# 05-MODEM.net
KiCad netlist of a schematic drawn in Altium Designer
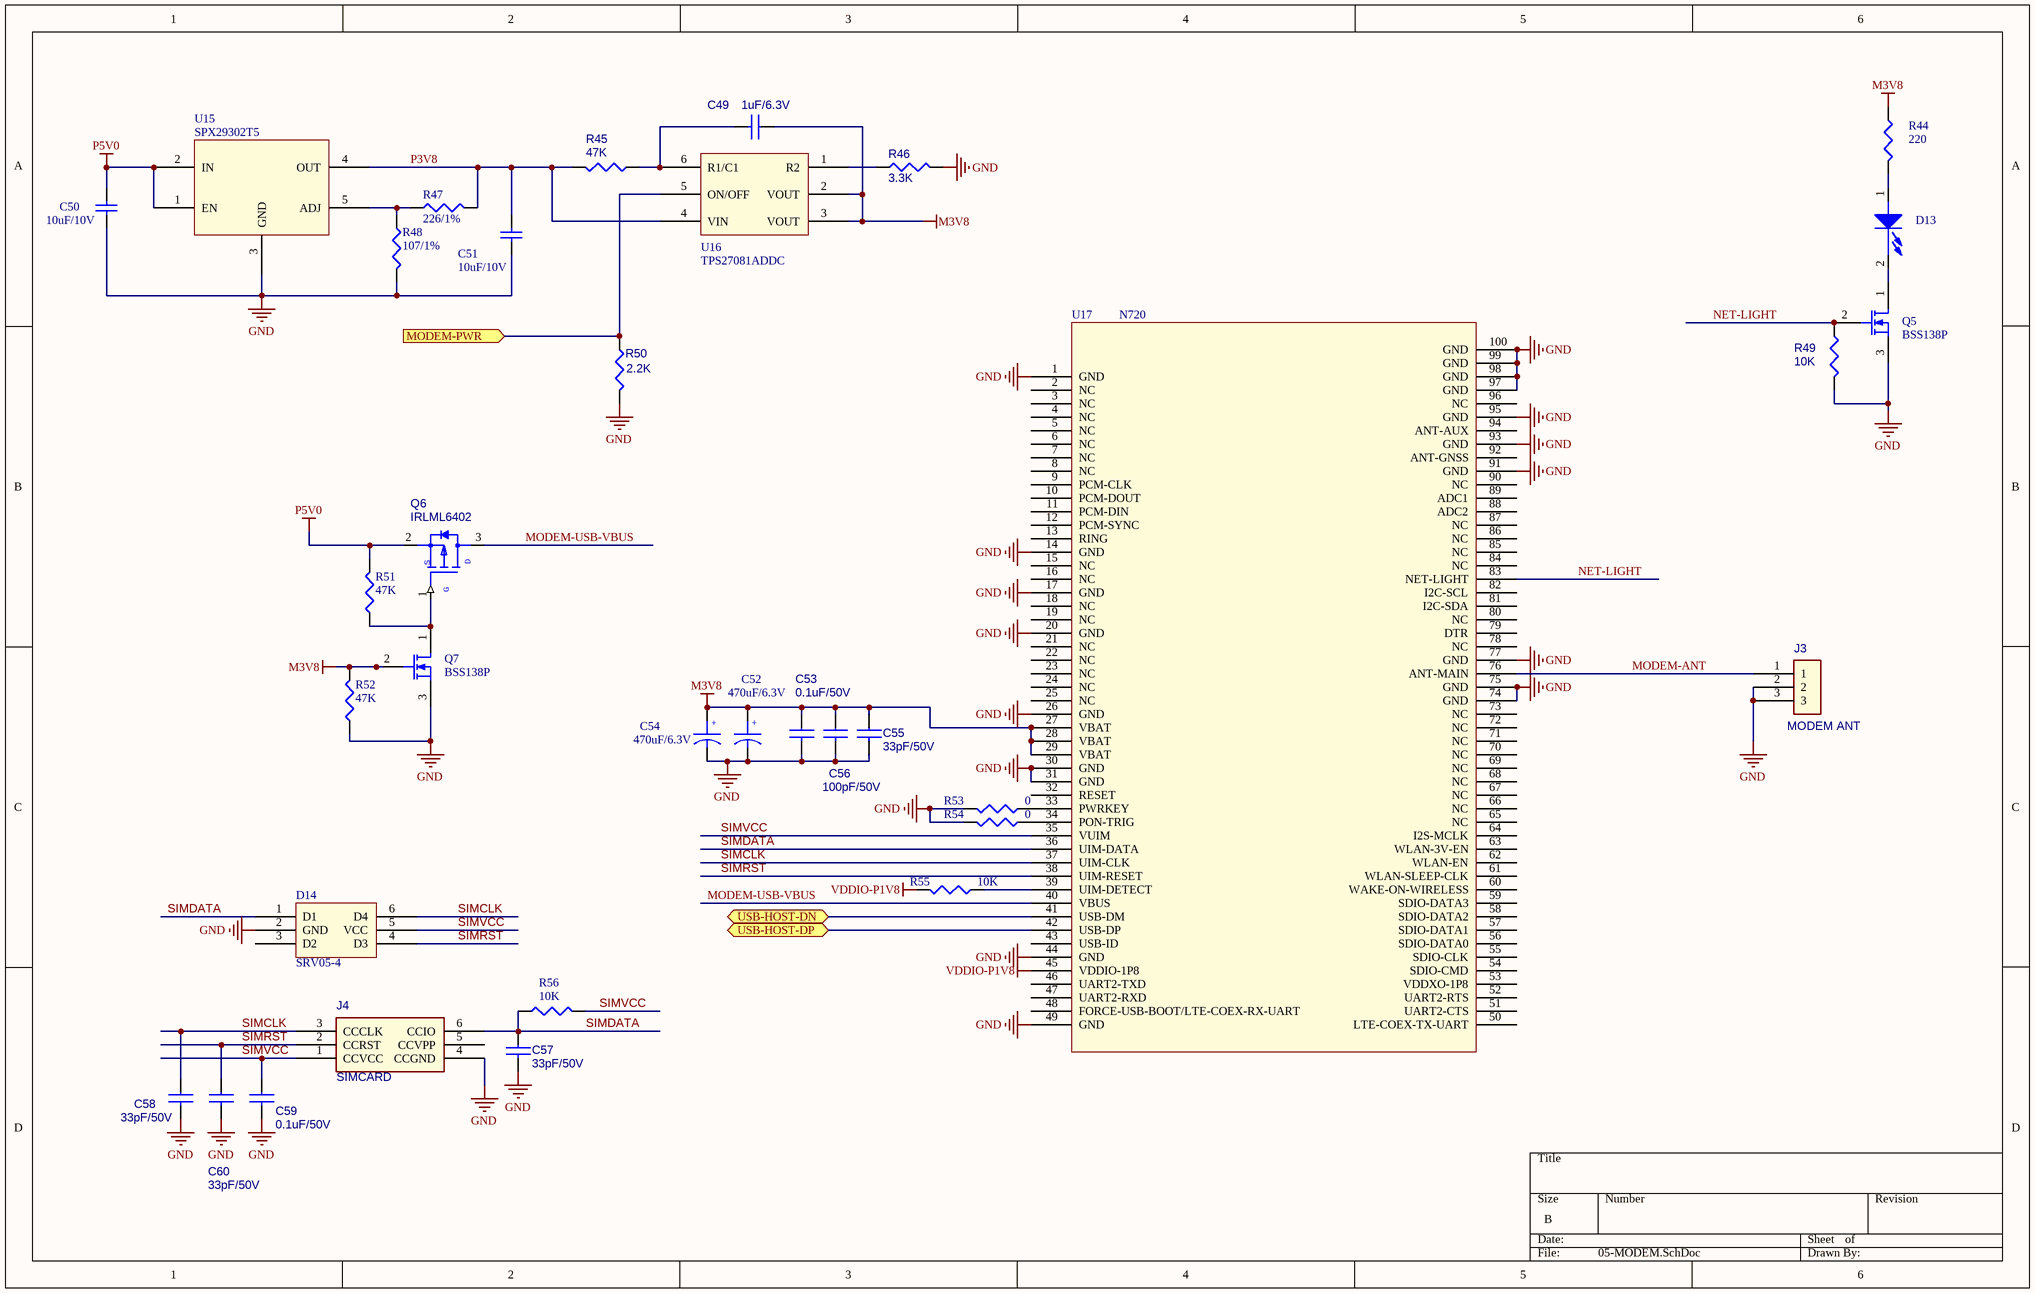
[diagram p0: 05-MODEM.SchDoc]

(export (version "E")
  (design (tool "Eeschema 10.0.6"))
  (components
    (comp (ref "C49") (value "1uF/6.3V") (footprint "0402") (libsource (lib "*") (part "P_CAP NP")))
    (comp (ref "C50")
      (value "10uF/10V")
      (footprint "0805")
      (description "Capacitor")
      (fields (field (name "PUBLISHER") "Altium Limited"))
      (libsource (lib "Miscellaneous Devices") (part "Cap"))
    )
    (comp (ref "C51")
      (value "10uF/10V")
      (footprint "0805")
      (description "Capacitor")
      (fields (field (name "PUBLISHER") "Altium Limited"))
      (libsource (lib "Miscellaneous Devices") (part "Cap"))
    )
    (comp (ref "C52") (value "470uF/6.3V") (libsource (lib "*") (part "CAP WP")))
    (comp (ref "C53") (value "0.1uF/50V") (libsource (lib "*") (part "P_CAP NP")))
    (comp (ref "C54") (value "470uF/6.3V") (libsource (lib "*") (part "CAP WP")))
    (comp (ref "C55") (value "33pF/50V") (libsource (lib "*") (part "P_CAP NP")))
    (comp (ref "C56") (value "100pF/50V") (libsource (lib "*") (part "P_CAP NP")))
    (comp (ref "C57") (value "33pF/50V") (libsource (lib "*") (part "P_CAP NP")))
    (comp (ref "C58") (value "33pF/50V") (libsource (lib "*") (part "P_CAP NP")))
    (comp (ref "C59") (value "0.1uF/50V") (libsource (lib "*") (part "P_CAP NP")))
    (comp (ref "C60") (value "33pF/50V") (libsource (lib "*") (part "P_CAP NP")))
    (comp (ref "D13") (value "LED GREEN") (footprint "LED-3MM") (libsource (lib "*") (part "LN01401_1")))
    (comp (ref "D14") (value "SRV05-4") (footprint "SOT23-6") (libsource (lib "Schlib") (part "SRV05-4")))
    (comp (ref "J3") (value "MODEM ANT") (footprint "ANT") (libsource (lib "*") (part "HRS_U_0.FL-R-SMT-10")))
    (comp (ref "J4") (value "SIMCARD") (footprint "SIM_CARD1") (libsource (lib "*") (part "SIMCARD")))
    (comp (ref "Q5")
      (value "BSS138P")
      (footprint "NPN")
      (description "N-Channel MOSFET")
      (fields (field (name "PUBLISHER") "Altium Limited"))
      (libsource (lib "Miscellaneous Devices") (part "MOSFET-N"))
    )
    (comp (ref "Q6")
      (value "IRLML6402")
      (footprint "MOSFET")
      (fields (field (name "PART NUMBER") "SB934010010"))
      (libsource (lib "*") (part "AO3401L_SOT23-3_0"))
    )
    (comp (ref "Q7")
      (value "BSS138P")
      (footprint "NPN")
      (description "N-Channel MOSFET")
      (fields (field (name "PUBLISHER") "Altium Limited"))
      (libsource (lib "Miscellaneous Devices") (part "MOSFET-N"))
    )
    (comp (ref "R44") (value "220") (footprint "0402") (libsource (lib "*") (part "CR16-1003FM")))
    (comp (ref "R45") (value "47K") (footprint "0402") (libsource (lib "*") (part "P_R")))
    (comp (ref "R46") (value "3.3K") (footprint "0402") (libsource (lib "*") (part "P_R")))
    (comp (ref "R47")
      (value "226/1%")
      (footprint "0402")
      (description "Resistor")
      (fields (field (name "PUBLISHER") "Altium Limited"))
      (libsource (lib "Miscellaneous Devices") (part "Res3"))
    )
    (comp (ref "R48")
      (value "107/1%")
      (footprint "0402")
      (description "Resistor")
      (fields (field (name "PUBLISHER") "Altium Limited"))
      (libsource (lib "Miscellaneous Devices") (part "Res3"))
    )
    (comp (ref "R49") (value "10K") (footprint "0402") (libsource (lib "*") (part "P_R")))
    (comp (ref "R50") (value "2.2K") (footprint "0402") (libsource (lib "*") (part "P_R")))
    (comp (ref "R51") (value "47K") (footprint "0402") (libsource (lib "*") (part "CR16-1003FM")))
    (comp (ref "R52") (value "47K") (footprint "0402") (libsource (lib "*") (part "CR16-1003FM")))
    (comp (ref "R53")
      (value "0")
      (footprint "0402")
      (description "Resistor")
      (fields (field (name "PUBLISHER") "Altium Limited"))
      (libsource (lib "Miscellaneous Devices") (part "Res3"))
    )
    (comp (ref "R54")
      (value "0")
      (footprint "0402")
      (description "Resistor")
      (fields (field (name "PUBLISHER") "Altium Limited"))
      (libsource (lib "Miscellaneous Devices") (part "Res3"))
    )
    (comp (ref "R55")
      (value "10K")
      (footprint "0402")
      (description "Resistor")
      (fields (field (name "PUBLISHER") "Altium Limited"))
      (libsource (lib "Miscellaneous Devices") (part "Res3"))
    )
    (comp (ref "R56")
      (value "10K")
      (footprint "0402")
      (description "Resistor")
      (fields (field (name "PUBLISHER") "Altium Limited"))
      (libsource (lib "Miscellaneous Devices") (part "Res3"))
    )
    (comp (ref "U15")
      (value "SPX29302T5")
      (footprint "TO-263")
      (libsource (lib "Schlib") (part "MIC29302AWU"))
    )
    (comp (ref "U16")
      (value "TPS27081ADDC")
      (footprint "SOT23-6")
      (libsource (lib "Schlib") (part "TPS27081A"))
    )
    (comp (ref "U17") (value "N720") (footprint "N720") (libsource (lib "Schlib") (part "N720")))
  )
  (nets
    (net (code "1") (name "/MODEM-ANT") (class "Default")
      (node (ref "J3") (pin "1") (pinfunction "1_1") (pintype "passive"))
      (node (ref "U17") (pin "76") (pinfunction "ANT-MAIN_76") (pintype "passive"))
    )
    (net (code "2") (name "/MODEM-PWR") (class "Default")
      (node (ref "R50") (pin "2") (pinfunction "2_2") (pintype "passive"))
      (node (ref "U16") (pin "5") (pinfunction "ON/OFF_5") (pintype "passive"))
    )
    (net (code "3") (name "/MODEM-USB-VBUS") (class "Default")
      (node (ref "Q6") (pin "3") (pinfunction "D_3") (pintype "passive"))
      (node (ref "U17") (pin "40") (pinfunction "VBUS_40") (pintype "passive"))
    )
    (net (code "4") (name "/NET-LIGHT") (class "Default")
      (node (ref "Q5") (pin "2") (pinfunction "G_2") (pintype "passive"))
      (node (ref "R49") (pin "2") (pinfunction "2_2") (pintype "passive"))
      (node (ref "U17") (pin "83") (pinfunction "NET-LIGHT_83") (pintype "passive"))
    )
    (net (code "5") (name "/P3V8") (class "Default")
      (node (ref "C51") (pin "2") (pinfunction "2_2") (pintype "passive"))
      (node (ref "R45") (pin "1") (pinfunction "1_1") (pintype "passive"))
      (node (ref "R47") (pin "2") (pinfunction "2_2") (pintype "passive"))
      (node (ref "U15") (pin "4") (pinfunction "OUT_4") (pintype "passive"))
      (node (ref "U16") (pin "4") (pinfunction "VIN_4") (pintype "passive"))
    )
    (net (code "6") (name "/SIMCLK") (class "Default")
      (node (ref "C58") (pin "1") (pinfunction "1_1") (pintype "passive"))
      (node (ref "D14") (pin "6") (pinfunction "D4_6") (pintype "passive"))
      (node (ref "J4") (pin "3") (pinfunction "CCCLK_3") (pintype "passive"))
      (node (ref "U17") (pin "37") (pinfunction "UIM-CLK_37") (pintype "passive"))
    )
    (net (code "7") (name "/SIMDATA") (class "Default")
      (node (ref "C57") (pin "1") (pinfunction "1_1") (pintype "passive"))
      (node (ref "D14") (pin "1") (pinfunction "D1_1") (pintype "passive"))
      (node (ref "J4") (pin "6") (pinfunction "CCIO_6") (pintype "passive"))
      (node (ref "R56") (pin "1") (pinfunction "1_1") (pintype "passive"))
      (node (ref "U17") (pin "36") (pinfunction "UIM-DATA_36") (pintype "passive"))
    )
    (net (code "8") (name "/SIMRST") (class "Default")
      (node (ref "C60") (pin "1") (pinfunction "1_1") (pintype "passive"))
      (node (ref "D14") (pin "4") (pinfunction "D3_4") (pintype "passive"))
      (node (ref "J4") (pin "2") (pinfunction "CCRST_2") (pintype "passive"))
      (node (ref "U17") (pin "38") (pinfunction "UIM-RESET_38") (pintype "passive"))
    )
    (net (code "9") (name "/SIMVCC") (class "Default")
      (node (ref "C59") (pin "1") (pinfunction "1_1") (pintype "passive"))
      (node (ref "D14") (pin "5") (pinfunction "VCC_5") (pintype "passive"))
      (node (ref "J4") (pin "1") (pinfunction "CCVCC_1") (pintype "passive"))
      (node (ref "R56") (pin "2") (pinfunction "2_2") (pintype "passive"))
      (node (ref "U17") (pin "35") (pinfunction "VUIM_35") (pintype "passive"))
    )
    (net (code "10") (name "/USB-HOST-DN") (class "Default")
      (node (ref "U17") (pin "41") (pinfunction "USB-DM_41") (pintype "passive"))
    )
    (net (code "11") (name "/USB-HOST-DP") (class "Default")
      (node (ref "U17") (pin "42") (pinfunction "USB-DP_42") (pintype "passive"))
    )
    (net (code "12") (name "GND") (class "Default")
      (node (ref "C50") (pin "1") (pinfunction "1_1") (pintype "passive"))
      (node (ref "C51") (pin "1") (pinfunction "1_1") (pintype "passive"))
      (node (ref "C52") (pin "2") (pinfunction "2_2") (pintype "passive"))
      (node (ref "C53") (pin "2") (pinfunction "2_2") (pintype "passive"))
      (node (ref "C54") (pin "2") (pinfunction "2_2") (pintype "passive"))
      (node (ref "C55") (pin "2") (pinfunction "2_2") (pintype "passive"))
      (node (ref "C56") (pin "2") (pinfunction "2_2") (pintype "passive"))
      (node (ref "C57") (pin "2") (pinfunction "2_2") (pintype "passive"))
      (node (ref "C58") (pin "2") (pinfunction "2_2") (pintype "passive"))
      (node (ref "C59") (pin "2") (pinfunction "2_2") (pintype "passive"))
      (node (ref "C60") (pin "2") (pinfunction "2_2") (pintype "passive"))
      (node (ref "D14") (pin "2") (pinfunction "GND_2") (pintype "passive"))
      (node (ref "J3") (pin "2") (pinfunction "2_2") (pintype "passive"))
      (node (ref "J3") (pin "3") (pinfunction "3_3") (pintype "passive"))
      (node (ref "J4") (pin "4") (pinfunction "CCGND_4") (pintype "passive"))
      (node (ref "Q5") (pin "3") (pinfunction "S_3") (pintype "passive"))
      (node (ref "Q7") (pin "3") (pinfunction "S_3") (pintype "passive"))
      (node (ref "R46") (pin "1") (pinfunction "1_1") (pintype "passive"))
      (node (ref "R48") (pin "2") (pinfunction "2_2") (pintype "passive"))
      (node (ref "R49") (pin "1") (pinfunction "1_1") (pintype "passive"))
      (node (ref "R50") (pin "1") (pinfunction "1_1") (pintype "passive"))
      (node (ref "R52") (pin "1") (pinfunction "1_1") (pintype "passive"))
      (node (ref "R53") (pin "2") (pinfunction "2_2") (pintype "passive"))
      (node (ref "R54") (pin "2") (pinfunction "2_2") (pintype "passive"))
      (node (ref "U15") (pin "3") (pinfunction "GND_3") (pintype "passive"))
      (node (ref "U17") (pin "1") (pinfunction "GND_1") (pintype "passive"))
      (node (ref "U17") (pin "100") (pinfunction "GND_100") (pintype "passive"))
      (node (ref "U17") (pin "14") (pinfunction "GND_14") (pintype "passive"))
      (node (ref "U17") (pin "17") (pinfunction "GND_17") (pintype "passive"))
      (node (ref "U17") (pin "20") (pinfunction "GND_20") (pintype "passive"))
      (node (ref "U17") (pin "26") (pinfunction "GND_26") (pintype "passive"))
      (node (ref "U17") (pin "30") (pinfunction "GND_30") (pintype "passive"))
      (node (ref "U17") (pin "31") (pinfunction "GND_31") (pintype "passive"))
      (node (ref "U17") (pin "44") (pinfunction "GND_44") (pintype "passive"))
      (node (ref "U17") (pin "49") (pinfunction "GND_49") (pintype "passive"))
      (node (ref "U17") (pin "74") (pinfunction "GND_74") (pintype "passive"))
      (node (ref "U17") (pin "75") (pinfunction "GND_75") (pintype "passive"))
      (node (ref "U17") (pin "77") (pinfunction "GND_77") (pintype "passive"))
      (node (ref "U17") (pin "91") (pinfunction "GND_91") (pintype "passive"))
      (node (ref "U17") (pin "93") (pinfunction "GND_93") (pintype "passive"))
      (node (ref "U17") (pin "95") (pinfunction "GND_95") (pintype "passive"))
      (node (ref "U17") (pin "97") (pinfunction "GND_97") (pintype "passive"))
      (node (ref "U17") (pin "98") (pinfunction "GND_98") (pintype "passive"))
      (node (ref "U17") (pin "99") (pinfunction "GND_99") (pintype "passive"))
    )
    (net (code "13") (name "M3V8") (class "Default")
      (node (ref "C49") (pin "1") (pinfunction "1_1") (pintype "passive"))
      (node (ref "C52") (pin "1") (pinfunction "1_1") (pintype "passive"))
      (node (ref "C53") (pin "1") (pinfunction "1_1") (pintype "passive"))
      (node (ref "C54") (pin "1") (pinfunction "1_1") (pintype "passive"))
      (node (ref "C55") (pin "1") (pinfunction "1_1") (pintype "passive"))
      (node (ref "C56") (pin "1") (pinfunction "1_1") (pintype "passive"))
      (node (ref "Q7") (pin "2") (pinfunction "G_2") (pintype "passive"))
      (node (ref "R44") (pin "1") (pinfunction "1_1") (pintype "passive"))
      (node (ref "R52") (pin "2") (pinfunction "2_2") (pintype "passive"))
      (node (ref "U16") (pin "2") (pinfunction "VOUT_2") (pintype "passive"))
      (node (ref "U16") (pin "3") (pinfunction "VOUT_3") (pintype "passive"))
      (node (ref "U17") (pin "27") (pinfunction "VBAT_27") (pintype "passive"))
      (node (ref "U17") (pin "28") (pinfunction "VBAT_28") (pintype "passive"))
      (node (ref "U17") (pin "29") (pinfunction "VBAT_29") (pintype "passive"))
    )
    (net (code "14") (name "Net-(D13-ANODE)") (class "Default")
      (node (ref "D13") (pin "1") (pinfunction "ANODE_1") (pintype "passive"))
      (node (ref "R44") (pin "2") (pinfunction "2_2") (pintype "passive"))
    )
    (net (code "15") (name "Net-(D13-CATHODE)") (class "Default")
      (node (ref "D13") (pin "2") (pinfunction "CATHODE_2") (pintype "passive"))
      (node (ref "Q5") (pin "1") (pinfunction "D_1") (pintype "passive"))
    )
    (net (code "16") (name "Net-(Q6-G)") (class "Default")
      (node (ref "Q6") (pin "1") (pinfunction "G_1") (pintype "input"))
      (node (ref "Q7") (pin "1") (pinfunction "D_1") (pintype "passive"))
      (node (ref "R51") (pin "1") (pinfunction "1_1") (pintype "passive"))
    )
    (net (code "17") (name "Net-(U15-ADJ)") (class "Default")
      (node (ref "R47") (pin "1") (pinfunction "1_1") (pintype "passive"))
      (node (ref "R48") (pin "1") (pinfunction "1_1") (pintype "passive"))
      (node (ref "U15") (pin "5") (pinfunction "ADJ_5") (pintype "passive"))
    )
    (net (code "18") (name "Net-(U16-R1{slash}C1)") (class "Default")
      (node (ref "C49") (pin "2") (pinfunction "2_2") (pintype "passive"))
      (node (ref "R45") (pin "2") (pinfunction "2_2") (pintype "passive"))
      (node (ref "U16") (pin "6") (pinfunction "R1/C1_6") (pintype "passive"))
    )
    (net (code "19") (name "Net-(U16-R2)") (class "Default")
      (node (ref "R46") (pin "2") (pinfunction "2_2") (pintype "passive"))
      (node (ref "U16") (pin "1") (pinfunction "R2_1") (pintype "passive"))
    )
    (net (code "20") (name "Net-(U17-PON-TRIG)") (class "Default")
      (node (ref "R54") (pin "1") (pinfunction "1_1") (pintype "passive"))
      (node (ref "U17") (pin "34") (pinfunction "PON-TRIG_34") (pintype "passive"))
    )
    (net (code "21") (name "Net-(U17-PWRKEY)") (class "Default")
      (node (ref "R53") (pin "1") (pinfunction "1_1") (pintype "passive"))
      (node (ref "U17") (pin "33") (pinfunction "PWRKEY_33") (pintype "passive"))
    )
    (net (code "22") (name "Net-(U17-UIM-DETECT)") (class "Default")
      (node (ref "R55") (pin "1") (pinfunction "1_1") (pintype "passive"))
      (node (ref "U17") (pin "39") (pinfunction "UIM-DETECT_39") (pintype "passive"))
    )
    (net (code "23") (name "P5V0") (class "Default")
      (node (ref "C50") (pin "2") (pinfunction "2_2") (pintype "passive"))
      (node (ref "Q6") (pin "2") (pinfunction "S_2") (pintype "passive"))
      (node (ref "R51") (pin "2") (pinfunction "2_2") (pintype "passive"))
      (node (ref "U15") (pin "1") (pinfunction "EN_1") (pintype "passive"))
      (node (ref "U15") (pin "2") (pinfunction "IN_2") (pintype "passive"))
    )
    (net (code "24") (name "VDDIO-P1V8") (class "Default")
      (node (ref "R55") (pin "2") (pinfunction "2_2") (pintype "passive"))
      (node (ref "U17") (pin "45") (pinfunction "VDDIO-1P8_45") (pintype "passive"))
    )
    (net (code "25") (name "unconnected-(D14-D2-Pad3)") (class "Default")
      (node (ref "D14") (pin "3") (pinfunction "D2_3") (pintype "passive"))
    )
    (net (code "26") (name "unconnected-(J4-CCVPP-Pad5)") (class "Default")
      (node (ref "J4") (pin "5") (pinfunction "CCVPP_5") (pintype "passive"))
    )
    (net (code "27") (name "unconnected-(U17-ADC1-Pad89)") (class "Default")
      (node (ref "U17") (pin "89") (pinfunction "ADC1_89") (pintype "passive"))
    )
    (net (code "28") (name "unconnected-(U17-ADC2-Pad88)") (class "Default")
      (node (ref "U17") (pin "88") (pinfunction "ADC2_88") (pintype "passive"))
    )
    (net (code "29") (name "unconnected-(U17-ANT-AUX-Pad94)") (class "Default")
      (node (ref "U17") (pin "94") (pinfunction "ANT-AUX_94") (pintype "passive"))
    )
    (net (code "30") (name "unconnected-(U17-ANT-GNSS-Pad92)") (class "Default")
      (node (ref "U17") (pin "92") (pinfunction "ANT-GNSS_92") (pintype "passive"))
    )
    (net (code "31") (name "unconnected-(U17-DTR-Pad79)") (class "Default")
      (node (ref "U17") (pin "79") (pinfunction "DTR_79") (pintype "passive"))
    )
    (net (code "32") (name "unconnected-(U17-FORCE-USB-BOOT{slash}LTE-COEX-RX-UART-Pad48)") (class "Default")
      (node (ref "U17") (pin "48") (pinfunction "FORCE-USB-BOOT/LTE-COEX-RX-UART_48") (pintype "passive"))
    )
    (net (code "33") (name "unconnected-(U17-I2C-SCL-Pad82)") (class "Default")
      (node (ref "U17") (pin "82") (pinfunction "I2C-SCL_82") (pintype "passive"))
    )
    (net (code "34") (name "unconnected-(U17-I2C-SDA-Pad81)") (class "Default")
      (node (ref "U17") (pin "81") (pinfunction "I2C-SDA_81") (pintype "passive"))
    )
    (net (code "35") (name "unconnected-(U17-I2S-MCLK-Pad64)") (class "Default")
      (node (ref "U17") (pin "64") (pinfunction "I2S-MCLK_64") (pintype "passive"))
    )
    (net (code "36") (name "unconnected-(U17-LTE-COEX-TX-UART-Pad50)") (class "Default")
      (node (ref "U17") (pin "50") (pinfunction "LTE-COEX-TX-UART_50") (pintype "passive"))
    )
    (net (code "37") (name "unconnected-(U17-NC-Pad2)") (class "Default")
      (node (ref "U17") (pin "2") (pinfunction "NC_2") (pintype "passive"))
    )
    (net (code "38") (name "unconnected-(U17-NC-Pad3)") (class "Default")
      (node (ref "U17") (pin "3") (pinfunction "NC_3") (pintype "passive"))
    )
    (net (code "39") (name "unconnected-(U17-NC-Pad4)") (class "Default")
      (node (ref "U17") (pin "4") (pinfunction "NC_4") (pintype "passive"))
    )
    (net (code "40") (name "unconnected-(U17-NC-Pad5)") (class "Default")
      (node (ref "U17") (pin "5") (pinfunction "NC_5") (pintype "passive"))
    )
    (net (code "41") (name "unconnected-(U17-NC-Pad6)") (class "Default")
      (node (ref "U17") (pin "6") (pinfunction "NC_6") (pintype "passive"))
    )
    (net (code "42") (name "unconnected-(U17-NC-Pad7)") (class "Default")
      (node (ref "U17") (pin "7") (pinfunction "NC_7") (pintype "passive"))
    )
    (net (code "43") (name "unconnected-(U17-NC-Pad8)") (class "Default")
      (node (ref "U17") (pin "8") (pinfunction "NC_8") (pintype "passive"))
    )
    (net (code "44") (name "unconnected-(U17-NC-Pad15)") (class "Default")
      (node (ref "U17") (pin "15") (pinfunction "NC_15") (pintype "passive"))
    )
    (net (code "45") (name "unconnected-(U17-NC-Pad16)") (class "Default")
      (node (ref "U17") (pin "16") (pinfunction "NC_16") (pintype "passive"))
    )
    (net (code "46") (name "unconnected-(U17-NC-Pad18)") (class "Default")
      (node (ref "U17") (pin "18") (pinfunction "NC_18") (pintype "passive"))
    )
    (net (code "47") (name "unconnected-(U17-NC-Pad19)") (class "Default")
      (node (ref "U17") (pin "19") (pinfunction "NC_19") (pintype "passive"))
    )
    (net (code "48") (name "unconnected-(U17-NC-Pad21)") (class "Default")
      (node (ref "U17") (pin "21") (pinfunction "NC_21") (pintype "passive"))
    )
    (net (code "49") (name "unconnected-(U17-NC-Pad22)") (class "Default")
      (node (ref "U17") (pin "22") (pinfunction "NC_22") (pintype "passive"))
    )
    (net (code "50") (name "unconnected-(U17-NC-Pad23)") (class "Default")
      (node (ref "U17") (pin "23") (pinfunction "NC_23") (pintype "passive"))
    )
    (net (code "51") (name "unconnected-(U17-NC-Pad24)") (class "Default")
      (node (ref "U17") (pin "24") (pinfunction "NC_24") (pintype "passive"))
    )
    (net (code "52") (name "unconnected-(U17-NC-Pad25)") (class "Default")
      (node (ref "U17") (pin "25") (pinfunction "NC_25") (pintype "passive"))
    )
    (net (code "53") (name "unconnected-(U17-NC-Pad65)") (class "Default")
      (node (ref "U17") (pin "65") (pinfunction "NC_65") (pintype "passive"))
    )
    (net (code "54") (name "unconnected-(U17-NC-Pad66)") (class "Default")
      (node (ref "U17") (pin "66") (pinfunction "NC_66") (pintype "passive"))
    )
    (net (code "55") (name "unconnected-(U17-NC-Pad67)") (class "Default")
      (node (ref "U17") (pin "67") (pinfunction "NC_67") (pintype "passive"))
    )
    (net (code "56") (name "unconnected-(U17-NC-Pad68)") (class "Default")
      (node (ref "U17") (pin "68") (pinfunction "NC_68") (pintype "passive"))
    )
    (net (code "57") (name "unconnected-(U17-NC-Pad69)") (class "Default")
      (node (ref "U17") (pin "69") (pinfunction "NC_69") (pintype "passive"))
    )
    (net (code "58") (name "unconnected-(U17-NC-Pad70)") (class "Default")
      (node (ref "U17") (pin "70") (pinfunction "NC_70") (pintype "passive"))
    )
    (net (code "59") (name "unconnected-(U17-NC-Pad71)") (class "Default")
      (node (ref "U17") (pin "71") (pinfunction "NC_71") (pintype "passive"))
    )
    (net (code "60") (name "unconnected-(U17-NC-Pad72)") (class "Default")
      (node (ref "U17") (pin "72") (pinfunction "NC_72") (pintype "passive"))
    )
    (net (code "61") (name "unconnected-(U17-NC-Pad73)") (class "Default")
      (node (ref "U17") (pin "73") (pinfunction "NC_73") (pintype "passive"))
    )
    (net (code "62") (name "unconnected-(U17-NC-Pad78)") (class "Default")
      (node (ref "U17") (pin "78") (pinfunction "NC_78") (pintype "passive"))
    )
    (net (code "63") (name "unconnected-(U17-NC-Pad80)") (class "Default")
      (node (ref "U17") (pin "80") (pinfunction "NC_80") (pintype "passive"))
    )
    (net (code "64") (name "unconnected-(U17-NC-Pad84)") (class "Default")
      (node (ref "U17") (pin "84") (pinfunction "NC_84") (pintype "passive"))
    )
    (net (code "65") (name "unconnected-(U17-NC-Pad85)") (class "Default")
      (node (ref "U17") (pin "85") (pinfunction "NC_85") (pintype "passive"))
    )
    (net (code "66") (name "unconnected-(U17-NC-Pad86)") (class "Default")
      (node (ref "U17") (pin "86") (pinfunction "NC_86") (pintype "passive"))
    )
    (net (code "67") (name "unconnected-(U17-NC-Pad87)") (class "Default")
      (node (ref "U17") (pin "87") (pinfunction "NC_87") (pintype "passive"))
    )
    (net (code "68") (name "unconnected-(U17-NC-Pad90)") (class "Default")
      (node (ref "U17") (pin "90") (pinfunction "NC_90") (pintype "passive"))
    )
    (net (code "69") (name "unconnected-(U17-NC-Pad96)") (class "Default")
      (node (ref "U17") (pin "96") (pinfunction "NC_96") (pintype "passive"))
    )
    (net (code "70") (name "unconnected-(U17-PCM-CLK-Pad9)") (class "Default")
      (node (ref "U17") (pin "9") (pinfunction "PCM-CLK_9") (pintype "passive"))
    )
    (net (code "71") (name "unconnected-(U17-PCM-DIN-Pad11)") (class "Default")
      (node (ref "U17") (pin "11") (pinfunction "PCM-DIN_11") (pintype "passive"))
    )
    (net (code "72") (name "unconnected-(U17-PCM-DOUT-Pad10)") (class "Default")
      (node (ref "U17") (pin "10") (pinfunction "PCM-DOUT_10") (pintype "passive"))
    )
    (net (code "73") (name "unconnected-(U17-PCM-SYNC-Pad12)") (class "Default")
      (node (ref "U17") (pin "12") (pinfunction "PCM-SYNC_12") (pintype "passive"))
    )
    (net (code "74") (name "unconnected-(U17-RESET-Pad32)") (class "Default")
      (node (ref "U17") (pin "32") (pinfunction "RESET_32") (pintype "passive"))
    )
    (net (code "75") (name "unconnected-(U17-RING-Pad13)") (class "Default")
      (node (ref "U17") (pin "13") (pinfunction "RING_13") (pintype "passive"))
    )
    (net (code "76") (name "unconnected-(U17-SDIO-CLK-Pad55)") (class "Default")
      (node (ref "U17") (pin "55") (pinfunction "SDIO-CLK_55") (pintype "passive"))
    )
    (net (code "77") (name "unconnected-(U17-SDIO-CMD-Pad54)") (class "Default")
      (node (ref "U17") (pin "54") (pinfunction "SDIO-CMD_54") (pintype "passive"))
    )
    (net (code "78") (name "unconnected-(U17-SDIO-DATA0-Pad56)") (class "Default")
      (node (ref "U17") (pin "56") (pinfunction "SDIO-DATA0_56") (pintype "passive"))
    )
    (net (code "79") (name "unconnected-(U17-SDIO-DATA1-Pad57)") (class "Default")
      (node (ref "U17") (pin "57") (pinfunction "SDIO-DATA1_57") (pintype "passive"))
    )
    (net (code "80") (name "unconnected-(U17-SDIO-DATA2-Pad58)") (class "Default")
      (node (ref "U17") (pin "58") (pinfunction "SDIO-DATA2_58") (pintype "passive"))
    )
    (net (code "81") (name "unconnected-(U17-SDIO-DATA3-Pad59)") (class "Default")
      (node (ref "U17") (pin "59") (pinfunction "SDIO-DATA3_59") (pintype "passive"))
    )
    (net (code "82") (name "unconnected-(U17-UART2-CTS-Pad51)") (class "Default")
      (node (ref "U17") (pin "51") (pinfunction "UART2-CTS_51") (pintype "passive"))
    )
    (net (code "83") (name "unconnected-(U17-UART2-RTS-Pad52)") (class "Default")
      (node (ref "U17") (pin "52") (pinfunction "UART2-RTS_52") (pintype "passive"))
    )
    (net (code "84") (name "unconnected-(U17-UART2-RXD-Pad47)") (class "Default")
      (node (ref "U17") (pin "47") (pinfunction "UART2-RXD_47") (pintype "passive"))
    )
    (net (code "85") (name "unconnected-(U17-UART2-TXD-Pad46)") (class "Default")
      (node (ref "U17") (pin "46") (pinfunction "UART2-TXD_46") (pintype "passive"))
    )
    (net (code "86") (name "unconnected-(U17-USB-ID-Pad43)") (class "Default")
      (node (ref "U17") (pin "43") (pinfunction "USB-ID_43") (pintype "passive"))
    )
    (net (code "87") (name "unconnected-(U17-VDDXO-1P8-Pad53)") (class "Default")
      (node (ref "U17") (pin "53") (pinfunction "VDDXO-1P8_53") (pintype "passive"))
    )
    (net (code "88") (name "unconnected-(U17-WAKE-ON-WIRELESS-Pad60)") (class "Default")
      (node (ref "U17") (pin "60") (pinfunction "WAKE-ON-WIRELESS_60") (pintype "passive"))
    )
    (net (code "89") (name "unconnected-(U17-WLAN-3V-EN-Pad63)") (class "Default")
      (node (ref "U17") (pin "63") (pinfunction "WLAN-3V-EN_63") (pintype "passive"))
    )
    (net (code "90") (name "unconnected-(U17-WLAN-EN-Pad62)") (class "Default")
      (node (ref "U17") (pin "62") (pinfunction "WLAN-EN_62") (pintype "passive"))
    )
    (net (code "91") (name "unconnected-(U17-WLAN-SLEEP-CLK-Pad61)") (class "Default")
      (node (ref "U17") (pin "61") (pinfunction "WLAN-SLEEP-CLK_61") (pintype "passive"))
    )
  )
)
